# POWER_USB_USART.net
KiCad netlist of a schematic drawn in Altium Designer
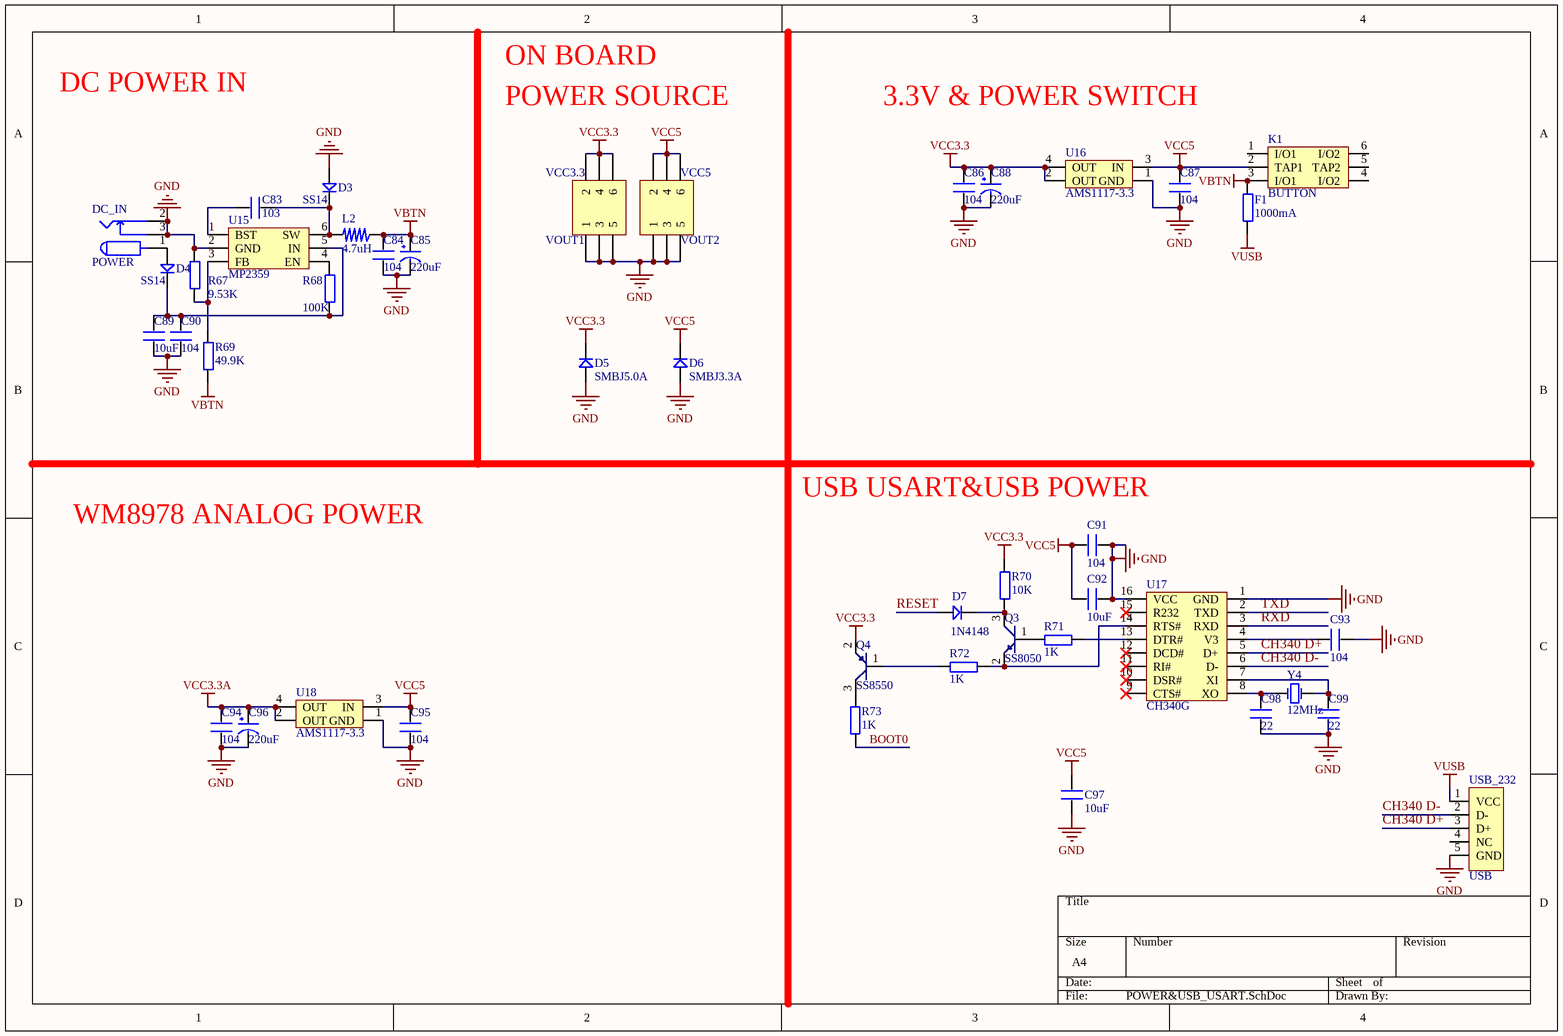
[diagram p0: POWER&USB_USART.SchDoc]

(export (version "E")
  (design (tool "Eeschema 10.0.6"))
  (components
    (comp (ref "C83") (value "103") (footprint "R0603") (libsource (lib "Explorer STM32F407封装库") (part "C")))
    (comp (ref "C84") (value "104") (footprint "R0603") (libsource (lib "Explorer STM32F407封装库") (part "C")))
    (comp (ref "C85")
      (value "220uF")
      (footprint "CC6.56.5")
      (libsource (lib "Explorer STM32F407封装库") (part "CAP"))
    )
    (comp (ref "C86") (value "104") (footprint "R0603") (libsource (lib "Explorer STM32F407封装库") (part "C")))
    (comp (ref "C87") (value "104") (footprint "R0603") (libsource (lib "Explorer STM32F407封装库") (part "C")))
    (comp (ref "C88")
      (value "220uF")
      (footprint "CC6.56.5")
      (libsource (lib "Explorer STM32F407封装库") (part "CAP"))
    )
    (comp (ref "C89")
      (value "10uF")
      (footprint "ZH_library:1206")
      (libsource (lib "Explorer STM32F407封装库") (part "C"))
    )
    (comp (ref "C90") (value "104") (footprint "R0603") (libsource (lib "Explorer STM32F407封装库") (part "C")))
    (comp (ref "C91") (value "104") (footprint "R0603") (libsource (lib "战舰STM32开发板底板封装库") (part "C")))
    (comp (ref "C92")
      (value "10uF")
      (footprint "ZH_library:1206")
      (libsource (lib "战舰STM32开发板底板封装库") (part "C"))
    )
    (comp (ref "C93") (value "104") (footprint "R0603") (libsource (lib "战舰STM32开发板底板封装库") (part "C")))
    (comp (ref "C94") (value "104") (footprint "R0603") (libsource (lib "Explorer STM32F407封装库") (part "C")))
    (comp (ref "C95") (value "104") (footprint "R0603") (libsource (lib "Explorer STM32F407封装库") (part "C")))
    (comp (ref "C96")
      (value "220uF")
      (footprint "CC6.56.5")
      (libsource (lib "Explorer STM32F407封装库") (part "CAP"))
    )
    (comp (ref "C97")
      (value "10uF")
      (footprint "ZH_library:1206")
      (libsource (lib "战舰STM32开发板底板封装库") (part "C"))
    )
    (comp (ref "C98") (value "22") (footprint "R0603") (libsource (lib "战舰STM32开发板底板封装库") (part "C")))
    (comp (ref "C99") (value "22") (footprint "R0603") (libsource (lib "战舰STM32开发板底板封装库") (part "C")))
    (comp (ref "D3")
      (value "SS14")
      (footprint "EXPLORER:DIODE_3*5.3")
      (libsource (lib "Explorer STM32F407封装库") (part "D"))
    )
    (comp (ref "D4")
      (value "SS14")
      (footprint "EXPLORER:DIODE_3*5.3")
      (libsource (lib "Explorer STM32F407封装库") (part "D"))
    )
    (comp (ref "D5")
      (value "SMBJ5.0A")
      (footprint "EXPLORER:SMBJ")
      (libsource (lib "Explorer STM32F407封装库") (part "D"))
    )
    (comp (ref "D6")
      (value "SMBJ3.3A")
      (footprint "EXPLORER:SMBJ")
      (libsource (lib "Explorer STM32F407封装库") (part "D"))
    )
    (comp (ref "D7") (value "1N4148") (footprint "DIODE_SOP") (libsource (lib "战舰STM32开发板底板封装库") (part "D")))
    (comp (ref "DC_IN")
      (value "POWER")
      (footprint "DC10B")
      (libsource (lib "Explorer STM32F407封装库") (part "POW"))
    )
    (comp (ref "F1")
      (value "1000mA")
      (footprint "ZH_library:1206")
      (libsource (lib "Explorer STM32F407封装库") (part "R"))
    )
    (comp (ref "K1")
      (value "BUTTON")
      (footprint "BTN8.5*8.5")
      (libsource (lib "Explorer STM32F407封装库") (part "BUTTON"))
    )
    (comp (ref "L2")
      (value "4.7uH")
      (footprint "L_SOP74")
      (libsource (lib "Explorer STM32F407封装库") (part "L_SOP"))
    )
    (comp (ref "Q3")
      (value "SS8050")
      (footprint "ZH_library:SOT23-3")
      (libsource (lib "ZH_library") (part "SS8050"))
    )
    (comp (ref "Q4")
      (value "SS8550")
      (footprint "ZH_library:SOT23-3")
      (libsource (lib "ZH_library") (part "SS8550"))
    )
    (comp (ref "R67")
      (value "9.53K")
      (footprint "R0603")
      (libsource (lib "Explorer STM32F407封装库") (part "R"))
    )
    (comp (ref "R68") (value "100K") (footprint "R0603") (libsource (lib "Explorer STM32F407封装库") (part "R")))
    (comp (ref "R69")
      (value "49.9K")
      (footprint "R0603")
      (libsource (lib "Explorer STM32F407封装库") (part "R"))
    )
    (comp (ref "R70") (value "10K") (footprint "R0603") (libsource (lib "战舰STM32开发板底板封装库") (part "R")))
    (comp (ref "R71") (value "1K") (footprint "R0603") (libsource (lib "战舰STM32开发板底板封装库") (part "R")))
    (comp (ref "R72") (value "1K") (footprint "R0603") (libsource (lib "战舰STM32开发板底板封装库") (part "R")))
    (comp (ref "R73") (value "1K") (footprint "R0603") (libsource (lib "战舰STM32开发板底板封装库") (part "R")))
    (comp (ref "U15")
      (value "MP2359")
      (footprint "SOT-23-6")
      (description "DC DC Step Down IC")
      (libsource (lib "Explorer STM32F407封装库") (part "MP2359"))
    )
    (comp (ref "U16")
      (value "AMS1117-3.3")
      (footprint "AMS1117")
      (libsource (lib "Explorer STM32F407封装库") (part "AMS1117"))
    )
    (comp (ref "U17")
      (value "CH340G")
      (footprint "SOP16M")
      (description "USB2UART")
      (libsource (lib "CORE") (part "CH340G"))
    )
    (comp (ref "U18")
      (value "AMS1117-3.3")
      (footprint "AMS1117")
      (libsource (lib "Explorer STM32F407封装库") (part "AMS1117"))
    )
    (comp (ref "USB_232")
      (value "USB")
      (footprint "ZH_library:MiniUSB/SM0.8-6H5")
      (libsource (lib "Explorer STM32F407封装库") (part "USB5"))
    )
    (comp (ref "VOUT1")
      (value "VCC3.3")
      (footprint "HDR2X3")
      (description "Header, 3-Pin, Dual row")
      (fields (field (name "PUBLISHER") "Altium Limited"))
      (libsource (lib "Explorer STM32F407封装库") (part "Header 3X2"))
    )
    (comp (ref "VOUT2")
      (value "VCC5")
      (footprint "HDR2X3")
      (description "Header, 3-Pin, Dual row")
      (fields (field (name "PUBLISHER") "Altium Limited"))
      (libsource (lib "Explorer STM32F407封装库") (part "Header 3X2"))
    )
    (comp (ref "Y4")
      (value "12MHz")
      (footprint "XTAL_US")
      (description "Crystal Oscillator")
      (fields (field (name "PUBLISHER") "Altium Limited"))
      (libsource (lib "战舰STM32开发板底板封装库") (part "XTAL_2"))
    )
  )
  (nets
    (net (code "1") (name "/BOOT0") (class "Default") (node (ref "R73") (pin "2") (pintype "passive")))
    (net (code "2") (name "/CH340 D+") (class "Default")
      (node (ref "U17") (pin "5") (pinfunction "D+_5") (pintype "passive"))
      (node (ref "USB_232") (pin "3") (pinfunction "D+_3") (pintype "passive"))
    )
    (net (code "3") (name "/CH340 D-") (class "Default")
      (node (ref "U17") (pin "6") (pinfunction "D-_6") (pintype "passive"))
      (node (ref "USB_232") (pin "2") (pinfunction "D-_2") (pintype "passive"))
    )
    (net (code "4") (name "/RESET") (class "Default") (node (ref "D7") (pin "1") (pintype "passive")))
    (net (code "5") (name "/RXD") (class "Default")
      (node (ref "U17") (pin "3") (pinfunction "RXD_3") (pintype "passive"))
    )
    (net (code "6") (name "/TXD") (class "Default")
      (node (ref "U17") (pin "2") (pinfunction "TXD_2") (pintype "passive"))
    )
    (net (code "7") (name "GND") (class "Default")
      (node (ref "C84") (pin "2") (pintype "passive"))
      (node (ref "C85") (pin "2") (pinfunction "GND_2") (pintype "passive"))
      (node (ref "C86") (pin "2") (pintype "passive"))
      (node (ref "C87") (pin "2") (pintype "passive"))
      (node (ref "C88") (pin "2") (pinfunction "GND_2") (pintype "passive"))
      (node (ref "C89") (pin "2") (pintype "passive"))
      (node (ref "C90") (pin "2") (pintype "passive"))
      (node (ref "C91") (pin "1") (pintype "passive"))
      (node (ref "C92") (pin "1") (pintype "passive"))
      (node (ref "C93") (pin "1") (pintype "passive"))
      (node (ref "C94") (pin "2") (pintype "passive"))
      (node (ref "C95") (pin "2") (pintype "passive"))
      (node (ref "C96") (pin "2") (pinfunction "GND_2") (pintype "passive"))
      (node (ref "C97") (pin "2") (pintype "passive"))
      (node (ref "C98") (pin "1") (pintype "passive"))
      (node (ref "C99") (pin "1") (pintype "passive"))
      (node (ref "D3") (pin "1") (pintype "passive"))
      (node (ref "D5") (pin "1") (pintype "passive"))
      (node (ref "D6") (pin "1") (pintype "passive"))
      (node (ref "DC_IN") (pin "2") (pintype "passive"))
      (node (ref "DC_IN") (pin "3") (pintype "passive"))
      (node (ref "R67") (pin "2") (pintype "passive"))
      (node (ref "U15") (pin "2") (pinfunction "GND_2") (pintype "passive"))
      (node (ref "U16") (pin "1") (pinfunction "GND_1") (pintype "passive"))
      (node (ref "U17") (pin "1") (pinfunction "GND_1") (pintype "passive"))
      (node (ref "U17") (pin "16") (pinfunction "VCC_16") (pintype "passive"))
      (node (ref "U18") (pin "1") (pinfunction "GND_1") (pintype "passive"))
      (node (ref "USB_232") (pin "5") (pinfunction "GND_5") (pintype "passive"))
      (node (ref "VOUT1") (pin "1") (pinfunction "1_1") (pintype "passive"))
      (node (ref "VOUT1") (pin "3") (pinfunction "3_3") (pintype "passive"))
      (node (ref "VOUT1") (pin "5") (pinfunction "5_5") (pintype "passive"))
      (node (ref "VOUT2") (pin "1") (pinfunction "1_1") (pintype "passive"))
      (node (ref "VOUT2") (pin "3") (pinfunction "3_3") (pintype "passive"))
      (node (ref "VOUT2") (pin "5") (pinfunction "5_5") (pintype "passive"))
    )
    (net (code "8") (name "Net-(D4-Pad1)") (class "Default")
      (node (ref "D4") (pin "1") (pintype "passive"))
      (node (ref "DC_IN") (pin "1") (pintype "passive"))
    )
    (net (code "9") (name "Net-(Q3-B)") (class "Default")
      (node (ref "Q3") (pin "1") (pinfunction "B_1") (pintype "passive"))
      (node (ref "R71") (pin "2") (pintype "passive"))
    )
    (net (code "10") (name "Net-(Q3-C)") (class "Default")
      (node (ref "D7") (pin "2") (pintype "passive"))
      (node (ref "Q3") (pin "3") (pinfunction "C_3") (pintype "passive"))
      (node (ref "R70") (pin "2") (pintype "passive"))
    )
    (net (code "11") (name "Net-(Q3-E)") (class "Default")
      (node (ref "Q3") (pin "2") (pinfunction "E_2") (pintype "passive"))
      (node (ref "R72") (pin "1") (pintype "passive"))
      (node (ref "U17") (pin "14") (pinfunction "RTS#_14") (pintype "passive"))
    )
    (net (code "12") (name "Net-(Q4-B)") (class "Default")
      (node (ref "Q4") (pin "1") (pinfunction "B_1") (pintype "passive"))
      (node (ref "R72") (pin "2") (pintype "passive"))
    )
    (net (code "13") (name "Net-(Q4-C)") (class "Default")
      (node (ref "Q4") (pin "3") (pinfunction "C_3") (pintype "passive"))
      (node (ref "R73") (pin "1") (pintype "passive"))
    )
    (net (code "14") (name "Net-(U15-BST)") (class "Default")
      (node (ref "C83") (pin "2") (pintype "passive"))
      (node (ref "U15") (pin "1") (pinfunction "BST_1") (pintype "passive"))
    )
    (net (code "15") (name "Net-(U15-EN)") (class "Default")
      (node (ref "R68") (pin "2") (pintype "passive"))
      (node (ref "U15") (pin "4") (pinfunction "EN_4") (pintype "passive"))
    )
    (net (code "16") (name "Net-(U15-FB)") (class "Default")
      (node (ref "R67") (pin "1") (pintype "passive"))
      (node (ref "R69") (pin "2") (pintype "passive"))
      (node (ref "U15") (pin "3") (pinfunction "FB_3") (pintype "passive"))
    )
    (net (code "17") (name "Net-(U15-IN)") (class "Default")
      (node (ref "C89") (pin "1") (pintype "passive"))
      (node (ref "C90") (pin "1") (pintype "passive"))
      (node (ref "D4") (pin "2") (pintype "passive"))
      (node (ref "R68") (pin "1") (pintype "passive"))
      (node (ref "U15") (pin "5") (pinfunction "IN_5") (pintype "passive"))
    )
    (net (code "18") (name "Net-(U15-SW)") (class "Default")
      (node (ref "C83") (pin "1") (pintype "passive"))
      (node (ref "D3") (pin "2") (pintype "passive"))
      (node (ref "L2") (pin "2") (pinfunction "2_2") (pintype "passive"))
      (node (ref "U15") (pin "6") (pinfunction "SW_6") (pintype "passive"))
    )
    (net (code "19") (name "Net-(U17-DTR#)") (class "Default")
      (node (ref "R71") (pin "1") (pintype "passive"))
      (node (ref "U17") (pin "13") (pinfunction "DTR#_13") (pintype "passive"))
    )
    (net (code "20") (name "Net-(U17-V3)") (class "Default")
      (node (ref "C93") (pin "2") (pintype "passive"))
      (node (ref "U17") (pin "4") (pinfunction "V3_4") (pintype "passive"))
    )
    (net (code "21") (name "Net-(U17-XI)") (class "Default")
      (node (ref "C99") (pin "2") (pintype "passive"))
      (node (ref "U17") (pin "7") (pinfunction "XI_7") (pintype "passive"))
      (node (ref "Y4") (pin "1") (pinfunction "OSC1_1") (pintype "passive"))
    )
    (net (code "22") (name "Net-(U17-XO)") (class "Default")
      (node (ref "C98") (pin "2") (pintype "passive"))
      (node (ref "U17") (pin "8") (pinfunction "XO_8") (pintype "passive"))
      (node (ref "Y4") (pin "2") (pinfunction "OSC2_2") (pintype "passive"))
    )
    (net (code "23") (name "VBTN") (class "Default")
      (node (ref "C84") (pin "1") (pintype "passive"))
      (node (ref "C85") (pin "1") (pinfunction "VCC_1") (pintype "passive"))
      (node (ref "F1") (pin "2") (pintype "passive"))
      (node (ref "K1") (pin "3") (pinfunction "I/O1_3") (pintype "passive"))
      (node (ref "L2") (pin "1") (pinfunction "1_1") (pintype "passive"))
      (node (ref "R69") (pin "1") (pintype "passive"))
    )
    (net (code "24") (name "VCC3.3") (class "Default")
      (node (ref "C86") (pin "1") (pintype "passive"))
      (node (ref "C88") (pin "1") (pinfunction "VCC_1") (pintype "passive"))
      (node (ref "D5") (pin "2") (pintype "passive"))
      (node (ref "Q4") (pin "2") (pinfunction "E_2") (pintype "passive"))
      (node (ref "R70") (pin "1") (pintype "passive"))
      (node (ref "U16") (pin "2") (pinfunction "OUT_2") (pintype "passive"))
      (node (ref "U16") (pin "4") (pinfunction "OUT_4") (pintype "passive"))
      (node (ref "VOUT1") (pin "2") (pinfunction "2_2") (pintype "passive"))
      (node (ref "VOUT1") (pin "4") (pinfunction "4_4") (pintype "passive"))
      (node (ref "VOUT1") (pin "6") (pinfunction "6_6") (pintype "passive"))
    )
    (net (code "25") (name "VCC3.3A") (class "Default")
      (node (ref "C94") (pin "1") (pintype "passive"))
      (node (ref "C96") (pin "1") (pinfunction "VCC_1") (pintype "passive"))
      (node (ref "U18") (pin "2") (pinfunction "OUT_2") (pintype "passive"))
      (node (ref "U18") (pin "4") (pinfunction "OUT_4") (pintype "passive"))
    )
    (net (code "26") (name "VCC5") (class "Default")
      (node (ref "C87") (pin "1") (pintype "passive"))
      (node (ref "C91") (pin "2") (pintype "passive"))
      (node (ref "C92") (pin "2") (pintype "passive"))
      (node (ref "C95") (pin "1") (pintype "passive"))
      (node (ref "C97") (pin "1") (pintype "passive"))
      (node (ref "D6") (pin "2") (pintype "passive"))
      (node (ref "K1") (pin "2") (pinfunction "TAP1_2") (pintype "passive"))
      (node (ref "U16") (pin "3") (pinfunction "IN_3") (pintype "passive"))
      (node (ref "U18") (pin "3") (pinfunction "IN_3") (pintype "passive"))
      (node (ref "VOUT2") (pin "2") (pinfunction "2_2") (pintype "passive"))
      (node (ref "VOUT2") (pin "4") (pinfunction "4_4") (pintype "passive"))
      (node (ref "VOUT2") (pin "6") (pinfunction "6_6") (pintype "passive"))
    )
    (net (code "27") (name "VUSB") (class "Default")
      (node (ref "F1") (pin "1") (pintype "passive"))
      (node (ref "USB_232") (pin "1") (pinfunction "VCC_1") (pintype "passive"))
    )
    (net (code "28") (name "unconnected-(K1-I{slash}O1-Pad1)") (class "Default")
      (node (ref "K1") (pin "1") (pinfunction "I/O1_1") (pintype "passive"))
    )
    (net (code "29") (name "unconnected-(K1-I{slash}O2-Pad4)") (class "Default")
      (node (ref "K1") (pin "4") (pinfunction "I/O2_4") (pintype "passive"))
    )
    (net (code "30") (name "unconnected-(K1-I{slash}O2-Pad6)") (class "Default")
      (node (ref "K1") (pin "6") (pinfunction "I/O2_6") (pintype "passive"))
    )
    (net (code "31") (name "unconnected-(K1-TAP2-Pad5)") (class "Default")
      (node (ref "K1") (pin "5") (pinfunction "TAP2_5") (pintype "passive"))
    )
    (net (code "32") (name "unconnected-(U17-CTS#-Pad9)") (class "Default")
      (node (ref "U17") (pin "9") (pinfunction "CTS#_9") (pintype "passive+no_connect"))
    )
    (net (code "33") (name "unconnected-(U17-DCD#-Pad12)") (class "Default")
      (node (ref "U17") (pin "12") (pinfunction "DCD#_12") (pintype "passive+no_connect"))
    )
    (net (code "34") (name "unconnected-(U17-DSR#-Pad10)") (class "Default")
      (node (ref "U17") (pin "10") (pinfunction "DSR#_10") (pintype "passive+no_connect"))
    )
    (net (code "35") (name "unconnected-(U17-R232-Pad15)") (class "Default")
      (node (ref "U17") (pin "15") (pinfunction "R232_15") (pintype "passive+no_connect"))
    )
    (net (code "36") (name "unconnected-(U17-RI#-Pad11)") (class "Default")
      (node (ref "U17") (pin "11") (pinfunction "RI#_11") (pintype "passive+no_connect"))
    )
    (net (code "37") (name "unconnected-(USB_232-NC-Pad4)") (class "Default")
      (node (ref "USB_232") (pin "4") (pinfunction "NC_4") (pintype "passive"))
    )
  )
)
